# Sheet1.net
KiCad netlist of a schematic drawn in Altium Designer
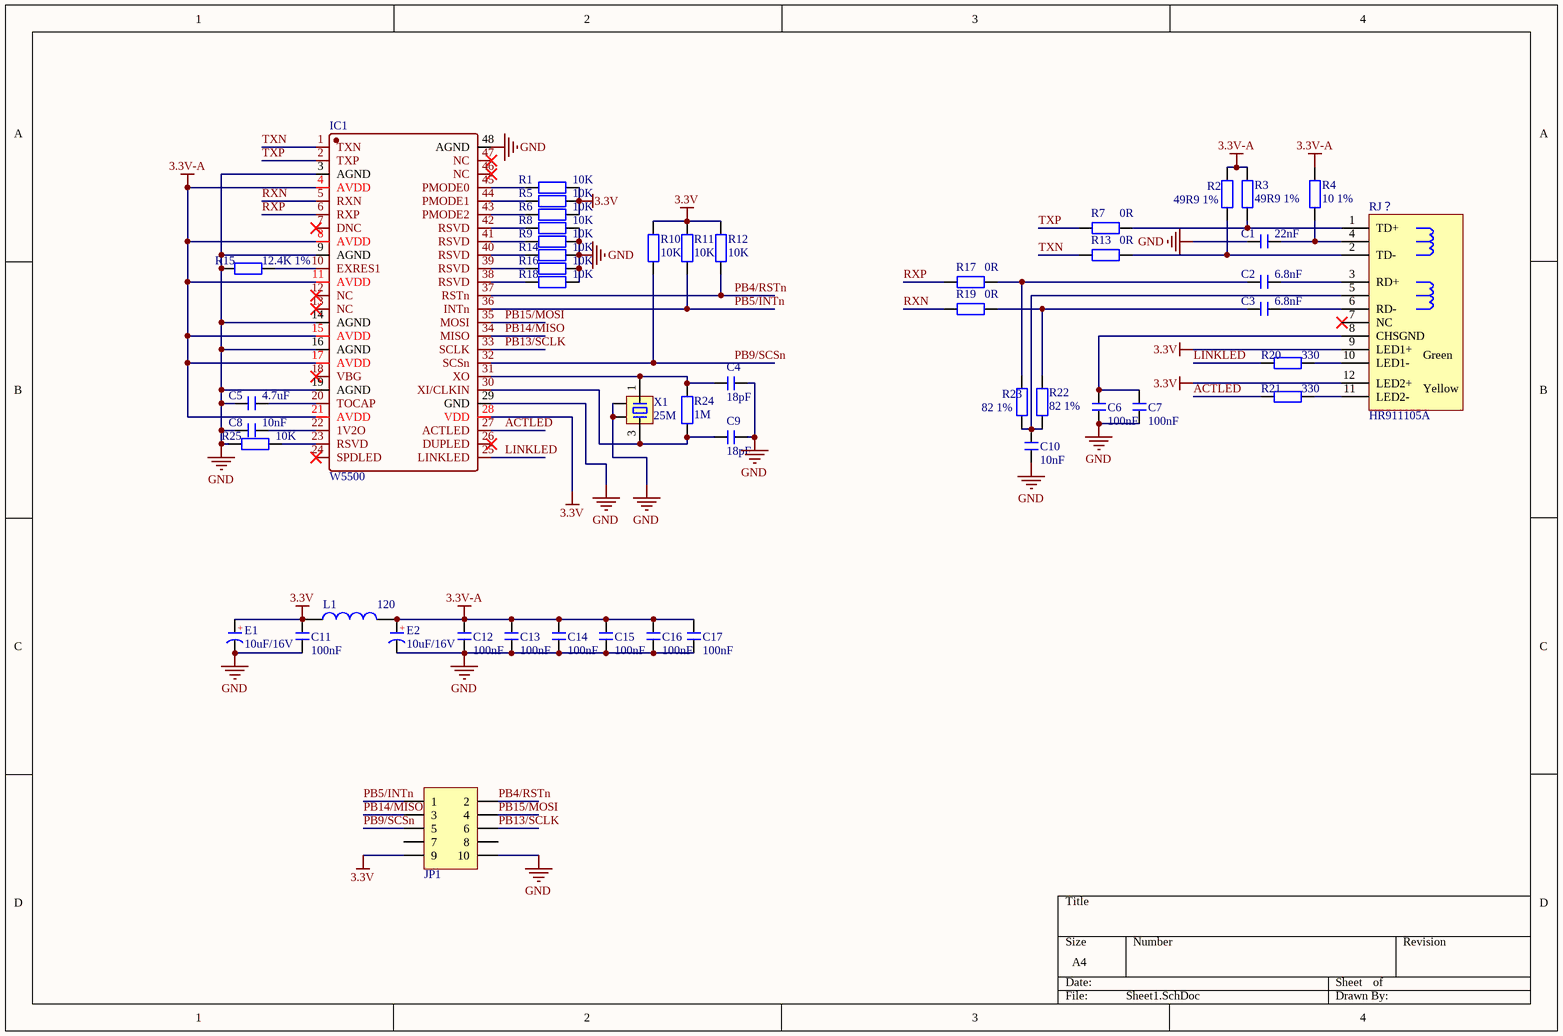
[diagram p0: Sheet1.SchDoc]

(export (version "E")
  (design (tool "Eeschema 10.0.6"))
  (components
    (comp (ref "C1")
      (value "22nF")
      (footprint "C 0402_L")
      (description "贴片电容")
      (libsource (lib "0.1 - 电阻-电容-电感") (part "C"))
    )
    (comp (ref "C2")
      (value "6.8nF")
      (footprint "C 0402_L")
      (description "贴片电容")
      (libsource (lib "0.1 - 电阻-电容-电感") (part "C"))
    )
    (comp (ref "C3")
      (value "6.8nF")
      (footprint "C 0402_L")
      (description "贴片电容")
      (libsource (lib "0.1 - 电阻-电容-电感") (part "C"))
    )
    (comp (ref "C4")
      (value "18pF")
      (footprint "C 0402_L")
      (description "贴片电容")
      (libsource (lib "0.1 - 电阻-电容-电感") (part "C"))
    )
    (comp (ref "C5")
      (value "4.7uF")
      (footprint "C 0402_L")
      (description "贴片电容")
      (libsource (lib "0.1 - 电阻-电容-电感") (part "C"))
    )
    (comp (ref "C6")
      (value "100nF")
      (footprint "C 0402_L")
      (description "贴片电容")
      (libsource (lib "0.1 - 电阻-电容-电感") (part "C"))
    )
    (comp (ref "C7")
      (value "100nF")
      (footprint "C 0402_L")
      (description "贴片电容")
      (libsource (lib "0.1 - 电阻-电容-电感") (part "C"))
    )
    (comp (ref "C8")
      (value "10nF")
      (footprint "C 0402_L")
      (description "贴片电容")
      (libsource (lib "0.1 - 电阻-电容-电感") (part "C"))
    )
    (comp (ref "C9")
      (value "18pF")
      (footprint "C 0402_L")
      (description "贴片电容")
      (libsource (lib "0.1 - 电阻-电容-电感") (part "C"))
    )
    (comp (ref "C10")
      (value "10nF")
      (footprint "C 0402_L")
      (description "贴片电容")
      (libsource (lib "0.1 - 电阻-电容-电感") (part "C"))
    )
    (comp (ref "C11")
      (value "100nF")
      (footprint "C 0402_L")
      (description "贴片电容")
      (libsource (lib "0.1 - 电阻-电容-电感") (part "C"))
    )
    (comp (ref "C12")
      (value "100nF")
      (footprint "C 0402_L")
      (description "贴片电容")
      (libsource (lib "0.1 - 电阻-电容-电感") (part "C"))
    )
    (comp (ref "C13")
      (value "100nF")
      (footprint "C 0402_L")
      (description "贴片电容")
      (libsource (lib "0.1 - 电阻-电容-电感") (part "C"))
    )
    (comp (ref "C14")
      (value "100nF")
      (footprint "C 0402_L")
      (description "贴片电容")
      (libsource (lib "0.1 - 电阻-电容-电感") (part "C"))
    )
    (comp (ref "C15")
      (value "100nF")
      (footprint "C 0402_L")
      (description "贴片电容")
      (libsource (lib "0.1 - 电阻-电容-电感") (part "C"))
    )
    (comp (ref "C16")
      (value "100nF")
      (footprint "C 0402_L")
      (description "贴片电容")
      (libsource (lib "0.1 - 电阻-电容-电感") (part "C"))
    )
    (comp (ref "C17")
      (value "100nF")
      (footprint "C 0402_L")
      (description "贴片电容")
      (libsource (lib "0.1 - 电阻-电容-电感") (part "C"))
    )
    (comp (ref "E1")
      (value "10uF/16V")
      (footprint "CD A(3216)")
      (description "贴片钽电容")
      (libsource (lib "0.1 - 电阻-电容-电感") (part "CT"))
    )
    (comp (ref "E2")
      (value "10uF/16V")
      (footprint "CD A(3216)")
      (description "贴片钽电容")
      (libsource (lib "0.1 - 电阻-电容-电感") (part "CT"))
    )
    (comp (ref "IC1")
      (value "W5500")
      (footprint "LQFP48-7*7")
      (description "网口芯片")
      (libsource (lib "1.0 - 常见芯片") (part "W5500"))
    )
    (comp (ref "JP1")
      (value "Header 5X2")
      (footprint "HDR2.54-LI-2x5P")
      (description "5*2P接插件")
      (fields (field (name "版权归属") "封装库来自淘宝 ID：黄晶宝石"))
      (libsource (lib "5.3 - 接插件-脚距2.54 (100mil) ") (part "Header 5X2"))
    )
    (comp (ref "L1")
      (value "120")
      (footprint "L 0402")
      (description "小功率贴片电感")
      (libsource (lib "0.1 - 电阻-电容-电感") (part "L"))
    )
    (comp (ref "R1")
      (value "10K")
      (footprint "R 0402_L")
      (description "贴片电阻")
      (fields (field (name "版权归属") "来自淘宝 ID：黄晶宝石"))
      (libsource (lib "0.1 - 电阻-电容-电感") (part "R"))
    )
    (comp (ref "R2")
      (value "49R9 1%")
      (footprint "R 0402_L")
      (description "贴片电阻")
      (fields (field (name "版权归属") "来自淘宝 ID：黄晶宝石"))
      (libsource (lib "0.1 - 电阻-电容-电感") (part "R"))
    )
    (comp (ref "R3")
      (value "49R9 1%")
      (footprint "R 0402_L")
      (description "贴片电阻")
      (fields (field (name "版权归属") "来自淘宝 ID：黄晶宝石"))
      (libsource (lib "0.1 - 电阻-电容-电感") (part "R"))
    )
    (comp (ref "R4")
      (value "10 1%")
      (footprint "R 0402_L")
      (description "贴片电阻")
      (fields (field (name "版权归属") "来自淘宝 ID：黄晶宝石"))
      (libsource (lib "0.1 - 电阻-电容-电感") (part "R"))
    )
    (comp (ref "R5")
      (value "10K")
      (footprint "R 0402_L")
      (description "贴片电阻")
      (fields (field (name "版权归属") "来自淘宝 ID：黄晶宝石"))
      (libsource (lib "0.1 - 电阻-电容-电感") (part "R"))
    )
    (comp (ref "R6")
      (value "10K")
      (footprint "R 0402_L")
      (description "贴片电阻")
      (fields (field (name "版权归属") "来自淘宝 ID：黄晶宝石"))
      (libsource (lib "0.1 - 电阻-电容-电感") (part "R"))
    )
    (comp (ref "R7")
      (value "0R")
      (footprint "R 0402_L")
      (description "贴片电阻")
      (fields (field (name "版权归属") "来自淘宝 ID：黄晶宝石"))
      (libsource (lib "0.1 - 电阻-电容-电感") (part "R"))
    )
    (comp (ref "R8")
      (value "10K")
      (footprint "R 0402_L")
      (description "贴片电阻")
      (fields (field (name "版权归属") "来自淘宝 ID：黄晶宝石"))
      (libsource (lib "0.1 - 电阻-电容-电感") (part "R"))
    )
    (comp (ref "R9")
      (value "10K")
      (footprint "R 0402_L")
      (description "贴片电阻")
      (fields (field (name "版权归属") "来自淘宝 ID：黄晶宝石"))
      (libsource (lib "0.1 - 电阻-电容-电感") (part "R"))
    )
    (comp (ref "R10")
      (value "10K")
      (footprint "R 0402_L")
      (description "贴片电阻")
      (fields (field (name "版权归属") "来自淘宝 ID：黄晶宝石"))
      (libsource (lib "0.1 - 电阻-电容-电感") (part "R"))
    )
    (comp (ref "R11")
      (value "10K")
      (footprint "R 0402_L")
      (description "贴片电阻")
      (fields (field (name "版权归属") "来自淘宝 ID：黄晶宝石"))
      (libsource (lib "0.1 - 电阻-电容-电感") (part "R"))
    )
    (comp (ref "R12")
      (value "10K")
      (footprint "R 0402_L")
      (description "贴片电阻")
      (fields (field (name "版权归属") "来自淘宝 ID：黄晶宝石"))
      (libsource (lib "0.1 - 电阻-电容-电感") (part "R"))
    )
    (comp (ref "R13")
      (value "0R")
      (footprint "R 0402_L")
      (description "贴片电阻")
      (fields (field (name "版权归属") "来自淘宝 ID：黄晶宝石"))
      (libsource (lib "0.1 - 电阻-电容-电感") (part "R"))
    )
    (comp (ref "R14")
      (value "10K")
      (footprint "R 0402_L")
      (description "贴片电阻")
      (fields (field (name "版权归属") "来自淘宝 ID：黄晶宝石"))
      (libsource (lib "0.1 - 电阻-电容-电感") (part "R"))
    )
    (comp (ref "R15")
      (value "12.4K 1%")
      (footprint "R 0402_L")
      (description "贴片电阻")
      (fields (field (name "版权归属") "来自淘宝 ID：黄晶宝石"))
      (libsource (lib "0.1 - 电阻-电容-电感") (part "R"))
    )
    (comp (ref "R16")
      (value "10K")
      (footprint "R 0402_L")
      (description "贴片电阻")
      (fields (field (name "版权归属") "来自淘宝 ID：黄晶宝石"))
      (libsource (lib "0.1 - 电阻-电容-电感") (part "R"))
    )
    (comp (ref "R17")
      (value "0R")
      (footprint "R 0402_L")
      (description "贴片电阻")
      (fields (field (name "版权归属") "来自淘宝 ID：黄晶宝石"))
      (libsource (lib "0.1 - 电阻-电容-电感") (part "R"))
    )
    (comp (ref "R18")
      (value "10K")
      (footprint "R 0402_L")
      (description "贴片电阻")
      (fields (field (name "版权归属") "来自淘宝 ID：黄晶宝石"))
      (libsource (lib "0.1 - 电阻-电容-电感") (part "R"))
    )
    (comp (ref "R19")
      (value "0R")
      (footprint "R 0402_L")
      (description "贴片电阻")
      (fields (field (name "版权归属") "来自淘宝 ID：黄晶宝石"))
      (libsource (lib "0.1 - 电阻-电容-电感") (part "R"))
    )
    (comp (ref "R20")
      (value "330")
      (footprint "R 0402_L")
      (description "贴片电阻")
      (fields (field (name "版权归属") "来自淘宝 ID：黄晶宝石"))
      (libsource (lib "0.1 - 电阻-电容-电感") (part "R"))
    )
    (comp (ref "R21")
      (value "330")
      (footprint "R 0402_L")
      (description "贴片电阻")
      (fields (field (name "版权归属") "来自淘宝 ID：黄晶宝石"))
      (libsource (lib "0.1 - 电阻-电容-电感") (part "R"))
    )
    (comp (ref "R22")
      (value "82 1%")
      (footprint "R 0402_L")
      (description "贴片电阻")
      (fields (field (name "版权归属") "来自淘宝 ID：黄晶宝石"))
      (libsource (lib "0.1 - 电阻-电容-电感") (part "R"))
    )
    (comp (ref "R23")
      (value "82 1%")
      (footprint "R 0402_L")
      (description "贴片电阻")
      (fields (field (name "版权归属") "来自淘宝 ID：黄晶宝石"))
      (libsource (lib "0.1 - 电阻-电容-电感") (part "R"))
    )
    (comp (ref "R24")
      (value "1M")
      (footprint "R 0402_L")
      (description "贴片电阻")
      (fields (field (name "版权归属") "来自淘宝 ID：黄晶宝石"))
      (libsource (lib "0.1 - 电阻-电容-电感") (part "R"))
    )
    (comp (ref "R25")
      (value "10K")
      (footprint "R 0402_L")
      (description "贴片电阻")
      (fields (field (name "版权归属") "来自淘宝 ID：黄晶宝石"))
      (libsource (lib "0.1 - 电阻-电容-电感") (part "R"))
    )
    (comp (ref "RJ？")
      (value "HR911105A")
      (footprint "RJ-45A12")
      (description "带灯以太网接口")
      (fields (field (name "版权归属") "封装库来自淘宝 ID：黄晶宝石"))
      (libsource (lib "0.8 - 以太网-音频-USB插座") (part "HR911105A"))
    )
    (comp (ref "X1")
      (value "25M")
      (footprint "OSC 3225-4P")
      (description "4脚无源晶振")
      (fields (field (name "版权归属") "封装库来自淘宝卖家 ID：黄晶宝石"))
      (libsource (lib "2.0 - 保险丝-晶振-光耦") (part "XTAL-4P"))
    )
  )
  (nets
    (net (code "2") (name "/ACTLED") (class "Default")
      (node (ref "IC1") (pin "27") (pinfunction "ACTLED_27") (pintype "passive"))
      (node (ref "R21") (pin "2") (pinfunction "2_2") (pintype "passive"))
    )
    (net (code "3") (name "/LINKLED") (class "Default")
      (node (ref "IC1") (pin "25") (pinfunction "LINKLED_25") (pintype "passive"))
      (node (ref "R20") (pin "2") (pinfunction "2_2") (pintype "passive"))
    )
    (net (code "4") (name "/PB4{slash}RSTn") (class "Default")
      (node (ref "IC1") (pin "37") (pinfunction "RSTn_37") (pintype "passive"))
      (node (ref "JP1") (pin "2") (pinfunction "2_2") (pintype "passive"))
      (node (ref "R12") (pin "1") (pinfunction "1_1") (pintype "passive"))
    )
    (net (code "5") (name "/PB5{slash}INTn") (class "Default")
      (node (ref "IC1") (pin "36") (pinfunction "INTn_36") (pintype "passive"))
      (node (ref "JP1") (pin "1") (pinfunction "1_1") (pintype "passive"))
      (node (ref "R11") (pin "1") (pinfunction "1_1") (pintype "passive"))
    )
    (net (code "6") (name "/PB9{slash}SCSn") (class "Default")
      (node (ref "IC1") (pin "32") (pinfunction "SCSn_32") (pintype "passive"))
      (node (ref "JP1") (pin "5") (pinfunction "5_5") (pintype "passive"))
      (node (ref "R10") (pin "1") (pinfunction "1_1") (pintype "passive"))
    )
    (net (code "7") (name "/PB13{slash}SCLK") (class "Default")
      (node (ref "IC1") (pin "33") (pinfunction "SCLK_33") (pintype "passive"))
      (node (ref "JP1") (pin "6") (pinfunction "6_6") (pintype "passive"))
    )
    (net (code "8") (name "/PB14{slash}MISO") (class "Default")
      (node (ref "IC1") (pin "34") (pinfunction "MISO_34") (pintype "passive"))
      (node (ref "JP1") (pin "3") (pinfunction "3_3") (pintype "passive"))
    )
    (net (code "9") (name "/PB15{slash}MOSI") (class "Default")
      (node (ref "IC1") (pin "35") (pinfunction "MOSI_35") (pintype "passive"))
      (node (ref "JP1") (pin "4") (pinfunction "4_4") (pintype "passive"))
    )
    (net (code "10") (name "/RXN") (class "Default")
      (node (ref "IC1") (pin "5") (pinfunction "RXN_5") (pintype "passive"))
      (node (ref "R19") (pin "2") (pinfunction "2_2") (pintype "passive"))
    )
    (net (code "11") (name "/RXP") (class "Default")
      (node (ref "IC1") (pin "6") (pinfunction "RXP_6") (pintype "passive"))
      (node (ref "R17") (pin "2") (pinfunction "2_2") (pintype "passive"))
    )
    (net (code "12") (name "/TXN") (class "Default")
      (node (ref "IC1") (pin "1") (pinfunction "TXN_1") (pintype "passive"))
      (node (ref "R13") (pin "2") (pinfunction "2_2") (pintype "passive"))
    )
    (net (code "13") (name "/TXP") (class "Default")
      (node (ref "IC1") (pin "2") (pinfunction "TXP_2") (pintype "passive"))
      (node (ref "R7") (pin "2") (pinfunction "2_2") (pintype "passive"))
    )
    (net (code "14") (name "3.3V") (class "Default")
      (node (ref "C11") (pin "2") (pinfunction "2_2") (pintype "passive"))
      (node (ref "E1") (pin "1") (pinfunction "A_1") (pintype "passive"))
      (node (ref "IC1") (pin "28") (pinfunction "VDD_28") (pintype "passive"))
      (node (ref "JP1") (pin "9") (pinfunction "9_9") (pintype "passive"))
      (node (ref "L1") (pin "1") (pinfunction "1_1") (pintype "passive"))
      (node (ref "R1") (pin "2") (pinfunction "2_2") (pintype "passive"))
      (node (ref "R10") (pin "2") (pinfunction "2_2") (pintype "passive"))
      (node (ref "R11") (pin "2") (pinfunction "2_2") (pintype "passive"))
      (node (ref "R12") (pin "2") (pinfunction "2_2") (pintype "passive"))
      (node (ref "R5") (pin "2") (pinfunction "2_2") (pintype "passive"))
      (node (ref "R6") (pin "2") (pinfunction "2_2") (pintype "passive"))
      (node (ref "RJ？") (pin "12") (pinfunction "LED2+_12") (pintype "passive"))
      (node (ref "RJ？") (pin "9") (pinfunction "LED1+_9") (pintype "passive"))
    )
    (net (code "15") (name "3.3V-A") (class "Default")
      (node (ref "C12") (pin "1") (pinfunction "1_1") (pintype "passive"))
      (node (ref "C13") (pin "1") (pinfunction "1_1") (pintype "passive"))
      (node (ref "C14") (pin "1") (pinfunction "1_1") (pintype "passive"))
      (node (ref "C15") (pin "1") (pinfunction "1_1") (pintype "passive"))
      (node (ref "C16") (pin "1") (pinfunction "1_1") (pintype "passive"))
      (node (ref "C17") (pin "1") (pinfunction "1_1") (pintype "passive"))
      (node (ref "E2") (pin "1") (pinfunction "A_1") (pintype "passive"))
      (node (ref "IC1") (pin "11") (pinfunction "AVDD_11") (pintype "passive"))
      (node (ref "IC1") (pin "15") (pinfunction "AVDD_15") (pintype "passive"))
      (node (ref "IC1") (pin "17") (pinfunction "AVDD_17") (pintype "passive"))
      (node (ref "IC1") (pin "21") (pinfunction "AVDD_21") (pintype "passive"))
      (node (ref "IC1") (pin "4") (pinfunction "AVDD_4") (pintype "passive"))
      (node (ref "IC1") (pin "8") (pinfunction "AVDD_8") (pintype "passive"))
      (node (ref "L1") (pin "2") (pinfunction "2_2") (pintype "passive"))
      (node (ref "R2") (pin "2") (pinfunction "2_2") (pintype "passive"))
      (node (ref "R3") (pin "2") (pinfunction "2_2") (pintype "passive"))
      (node (ref "R4") (pin "2") (pinfunction "2_2") (pintype "passive"))
    )
    (net (code "16") (name "GND") (class "Default")
      (node (ref "C1") (pin "2") (pinfunction "2_2") (pintype "passive"))
      (node (ref "C10") (pin "2") (pinfunction "2_2") (pintype "passive"))
      (node (ref "C11") (pin "1") (pinfunction "1_1") (pintype "passive"))
      (node (ref "C12") (pin "2") (pinfunction "2_2") (pintype "passive"))
      (node (ref "C13") (pin "2") (pinfunction "2_2") (pintype "passive"))
      (node (ref "C14") (pin "2") (pinfunction "2_2") (pintype "passive"))
      (node (ref "C15") (pin "2") (pinfunction "2_2") (pintype "passive"))
      (node (ref "C16") (pin "2") (pinfunction "2_2") (pintype "passive"))
      (node (ref "C17") (pin "2") (pinfunction "2_2") (pintype "passive"))
      (node (ref "C4") (pin "1") (pinfunction "1_1") (pintype "passive"))
      (node (ref "C5") (pin "2") (pinfunction "2_2") (pintype "passive"))
      (node (ref "C6") (pin "1") (pinfunction "1_1") (pintype "passive"))
      (node (ref "C7") (pin "1") (pinfunction "1_1") (pintype "passive"))
      (node (ref "C8") (pin "2") (pinfunction "2_2") (pintype "passive"))
      (node (ref "C9") (pin "1") (pinfunction "1_1") (pintype "passive"))
      (node (ref "E1") (pin "2") (pinfunction "K_2") (pintype "passive"))
      (node (ref "E2") (pin "2") (pinfunction "K_2") (pintype "passive"))
      (node (ref "IC1") (pin "14") (pinfunction "AGND_14") (pintype "passive"))
      (node (ref "IC1") (pin "16") (pinfunction "AGND_16") (pintype "passive"))
      (node (ref "IC1") (pin "19") (pinfunction "AGND_19") (pintype "passive"))
      (node (ref "IC1") (pin "29") (pinfunction "GND_29") (pintype "passive"))
      (node (ref "IC1") (pin "3") (pinfunction "AGND_3") (pintype "passive"))
      (node (ref "IC1") (pin "48") (pinfunction "AGND_48") (pintype "passive"))
      (node (ref "IC1") (pin "9") (pinfunction "AGND_9") (pintype "passive"))
      (node (ref "JP1") (pin "10") (pinfunction "10_10") (pintype "passive"))
      (node (ref "R14") (pin "2") (pinfunction "2_2") (pintype "passive"))
      (node (ref "R15") (pin "1") (pinfunction "1_1") (pintype "passive"))
      (node (ref "R16") (pin "2") (pinfunction "2_2") (pintype "passive"))
      (node (ref "R18") (pin "2") (pinfunction "2_2") (pintype "passive"))
      (node (ref "R25") (pin "1") (pinfunction "1_1") (pintype "passive"))
      (node (ref "R8") (pin "2") (pinfunction "2_2") (pintype "passive"))
      (node (ref "R9") (pin "2") (pinfunction "2_2") (pintype "passive"))
      (node (ref "X1") (pin "2") (pinfunction "2_2") (pintype "passive"))
      (node (ref "X1") (pin "4") (pinfunction "4_4") (pintype "passive"))
    )
    (net (code "17") (name "Net-(C1-Pad1)") (class "Default")
      (node (ref "C1") (pin "1") (pinfunction "1_1") (pintype "passive"))
      (node (ref "R4") (pin "1") (pinfunction "1_1") (pintype "passive"))
      (node (ref "RJ？") (pin "4") (pintype "passive"))
    )
    (net (code "18") (name "Net-(C2-Pad2)") (class "Default")
      (node (ref "C2") (pin "2") (pinfunction "2_2") (pintype "passive"))
      (node (ref "R17") (pin "1") (pinfunction "1_1") (pintype "passive"))
      (node (ref "R23") (pin "2") (pinfunction "2_2") (pintype "passive"))
    )
    (net (code "19") (name "Net-(C3-Pad2)") (class "Default")
      (node (ref "C3") (pin "2") (pinfunction "2_2") (pintype "passive"))
      (node (ref "R19") (pin "1") (pinfunction "1_1") (pintype "passive"))
      (node (ref "R22") (pin "1") (pinfunction "1_1") (pintype "passive"))
    )
    (net (code "20") (name "Net-(C10-Pad1)") (class "Default")
      (node (ref "C10") (pin "1") (pinfunction "1_1") (pintype "passive"))
      (node (ref "R22") (pin "2") (pinfunction "2_2") (pintype "passive"))
      (node (ref "R23") (pin "1") (pinfunction "1_1") (pintype "passive"))
      (node (ref "RJ？") (pin "5") (pintype "passive"))
    )
    (net (code "21") (name "Net-(IC1-1V2O)") (class "Default")
      (node (ref "C8") (pin "1") (pinfunction "1_1") (pintype "passive"))
      (node (ref "IC1") (pin "22") (pinfunction "1V2O_22") (pintype "passive"))
    )
    (net (code "22") (name "Net-(IC1-EXRES1)") (class "Default")
      (node (ref "IC1") (pin "10") (pinfunction "EXRES1_10") (pintype "passive"))
      (node (ref "R15") (pin "2") (pinfunction "2_2") (pintype "passive"))
    )
    (net (code "23") (name "Net-(IC1-PMODE0)") (class "Default")
      (node (ref "IC1") (pin "45") (pinfunction "PMODE0_45") (pintype "passive"))
      (node (ref "R1") (pin "1") (pinfunction "1_1") (pintype "passive"))
    )
    (net (code "24") (name "Net-(IC1-PMODE1)") (class "Default")
      (node (ref "IC1") (pin "44") (pinfunction "PMODE1_44") (pintype "passive"))
      (node (ref "R5") (pin "1") (pinfunction "1_1") (pintype "passive"))
    )
    (net (code "25") (name "Net-(IC1-PMODE2)") (class "Default")
      (node (ref "IC1") (pin "43") (pinfunction "PMODE2_43") (pintype "passive"))
      (node (ref "R6") (pin "1") (pinfunction "1_1") (pintype "passive"))
    )
    (net (code "26") (name "Net-(IC1-RSVD-Pad23)") (class "Default")
      (node (ref "IC1") (pin "23") (pinfunction "RSVD_23") (pintype "passive"))
      (node (ref "R25") (pin "2") (pinfunction "2_2") (pintype "passive"))
    )
    (net (code "27") (name "Net-(IC1-RSVD-Pad38)") (class "Default")
      (node (ref "IC1") (pin "38") (pinfunction "RSVD_38") (pintype "passive"))
      (node (ref "R18") (pin "1") (pinfunction "1_1") (pintype "passive"))
    )
    (net (code "28") (name "Net-(IC1-RSVD-Pad39)") (class "Default")
      (node (ref "IC1") (pin "39") (pinfunction "RSVD_39") (pintype "passive"))
      (node (ref "R16") (pin "1") (pinfunction "1_1") (pintype "passive"))
    )
    (net (code "29") (name "Net-(IC1-RSVD-Pad40)") (class "Default")
      (node (ref "IC1") (pin "40") (pinfunction "RSVD_40") (pintype "passive"))
      (node (ref "R14") (pin "1") (pinfunction "1_1") (pintype "passive"))
    )
    (net (code "30") (name "Net-(IC1-RSVD-Pad41)") (class "Default")
      (node (ref "IC1") (pin "41") (pinfunction "RSVD_41") (pintype "passive"))
      (node (ref "R9") (pin "1") (pinfunction "1_1") (pintype "passive"))
    )
    (net (code "31") (name "Net-(IC1-RSVD-Pad42)") (class "Default")
      (node (ref "IC1") (pin "42") (pinfunction "RSVD_42") (pintype "passive"))
      (node (ref "R8") (pin "1") (pinfunction "1_1") (pintype "passive"))
    )
    (net (code "32") (name "Net-(IC1-TOCAP)") (class "Default")
      (node (ref "C5") (pin "1") (pinfunction "1_1") (pintype "passive"))
      (node (ref "IC1") (pin "20") (pinfunction "TOCAP_20") (pintype "passive"))
    )
    (net (code "33") (name "Net-(IC1-XI{slash}CLKIN)") (class "Default")
      (node (ref "C9") (pin "2") (pinfunction "2_2") (pintype "passive"))
      (node (ref "IC1") (pin "30") (pinfunction "XI/CLKIN_30") (pintype "passive"))
      (node (ref "R24") (pin "1") (pinfunction "1_1") (pintype "passive"))
      (node (ref "X1") (pin "3") (pinfunction "3_3") (pintype "passive"))
    )
    (net (code "34") (name "Net-(IC1-XO)") (class "Default")
      (node (ref "C4") (pin "2") (pinfunction "2_2") (pintype "passive"))
      (node (ref "IC1") (pin "31") (pinfunction "XO_31") (pintype "passive"))
      (node (ref "R24") (pin "2") (pinfunction "2_2") (pintype "passive"))
      (node (ref "X1") (pin "1") (pinfunction "1_1") (pintype "passive"))
    )
    (net (code "35") (name "Net-(RJ？-CHSGND)") (class "Default")
      (node (ref "C6") (pin "2") (pinfunction "2_2") (pintype "passive"))
      (node (ref "C7") (pin "2") (pinfunction "2_2") (pintype "passive"))
      (node (ref "RJ？") (pin "8") (pinfunction "CHSGND_8") (pintype "passive"))
    )
    (net (code "36") (name "Net-(RJ？-LED1-)") (class "Default")
      (node (ref "R20") (pin "1") (pinfunction "1_1") (pintype "passive"))
      (node (ref "RJ？") (pin "10") (pinfunction "LED1-_10") (pintype "passive"))
    )
    (net (code "37") (name "Net-(RJ？-LED2-)") (class "Default")
      (node (ref "R21") (pin "1") (pinfunction "1_1") (pintype "passive"))
      (node (ref "RJ？") (pin "11") (pinfunction "LED2-_11") (pintype "passive"))
    )
    (net (code "38") (name "Net-(RJ？-RD+)") (class "Default")
      (node (ref "C2") (pin "1") (pinfunction "1_1") (pintype "passive"))
      (node (ref "RJ？") (pin "3") (pinfunction "RD+_3") (pintype "passive"))
    )
    (net (code "39") (name "Net-(RJ？-RD-)") (class "Default")
      (node (ref "C3") (pin "1") (pinfunction "1_1") (pintype "passive"))
      (node (ref "RJ？") (pin "6") (pinfunction "RD-_6") (pintype "passive"))
    )
    (net (code "40") (name "Net-(RJ？-TD+)") (class "Default")
      (node (ref "R3") (pin "1") (pinfunction "1_1") (pintype "passive"))
      (node (ref "R7") (pin "1") (pinfunction "1_1") (pintype "passive"))
      (node (ref "RJ？") (pin "1") (pinfunction "TD+_1") (pintype "passive"))
    )
    (net (code "41") (name "Net-(RJ？-TD-)") (class "Default")
      (node (ref "R13") (pin "1") (pinfunction "1_1") (pintype "passive"))
      (node (ref "R2") (pin "1") (pinfunction "1_1") (pintype "passive"))
      (node (ref "RJ？") (pin "2") (pinfunction "TD-_2") (pintype "passive"))
    )
    (net (code "42") (name "unconnected-(IC1-DNC-Pad7)") (class "Default")
      (node (ref "IC1") (pin "7") (pinfunction "DNC_7") (pintype "passive+no_connect"))
    )
    (net (code "43") (name "unconnected-(IC1-DUPLED-Pad26)") (class "Default")
      (node (ref "IC1") (pin "26") (pinfunction "DUPLED_26") (pintype "passive+no_connect"))
    )
    (net (code "44") (name "unconnected-(IC1-NC-Pad12)") (class "Default")
      (node (ref "IC1") (pin "12") (pinfunction "NC_12") (pintype "passive+no_connect"))
    )
    (net (code "45") (name "unconnected-(IC1-NC-Pad13)") (class "Default")
      (node (ref "IC1") (pin "13") (pinfunction "NC_13") (pintype "passive+no_connect"))
    )
    (net (code "46") (name "unconnected-(IC1-NC-Pad46)") (class "Default")
      (node (ref "IC1") (pin "46") (pinfunction "NC_46") (pintype "passive+no_connect"))
    )
    (net (code "47") (name "unconnected-(IC1-NC-Pad47)") (class "Default")
      (node (ref "IC1") (pin "47") (pinfunction "NC_47") (pintype "passive+no_connect"))
    )
    (net (code "48") (name "unconnected-(IC1-SPDLED-Pad24)") (class "Default")
      (node (ref "IC1") (pin "24") (pinfunction "SPDLED_24") (pintype "passive+no_connect"))
    )
    (net (code "49") (name "unconnected-(IC1-VBG-Pad18)") (class "Default")
      (node (ref "IC1") (pin "18") (pinfunction "VBG_18") (pintype "passive+no_connect"))
    )
    (net (code "50") (name "unconnected-(JP1-Pad7)") (class "Default")
      (node (ref "JP1") (pin "7") (pinfunction "7_7") (pintype "passive"))
    )
    (net (code "51") (name "unconnected-(JP1-Pad8)") (class "Default")
      (node (ref "JP1") (pin "8") (pinfunction "8_8") (pintype "passive"))
    )
    (net (code "52") (name "unconnected-(RJ？-NC-Pad7)") (class "Default")
      (node (ref "RJ？") (pin "7") (pinfunction "NC_7") (pintype "passive+no_connect"))
    )
  )
)
